# Battery.net
KiCad netlist of a schematic drawn in Altium Designer
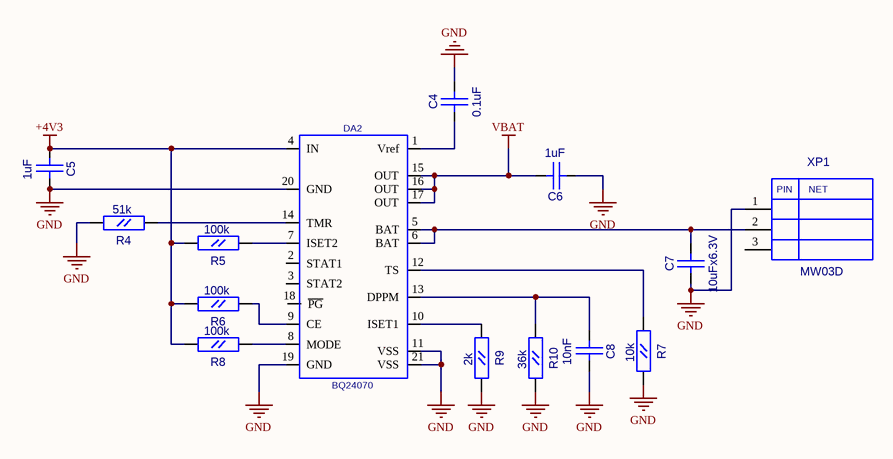
[diagram p0: Battery.SchDoc]

(export (version "E")
  (design (tool "Eeschema 10.0.6"))
  (components
    (comp (ref "C4")
      (value "0.1uF")
      (footprint "CC0603")
      (description "CC0603")
      (libsource (lib "gprs_modem_2") (part "CC0603"))
    )
    (comp (ref "C5")
      (value "1uF")
      (footprint "CC0603")
      (description "CC0603")
      (libsource (lib "gprs_modem_2") (part "CC0603"))
    )
    (comp (ref "C6")
      (value "1uF")
      (footprint "CC0603")
      (description "CC0603")
      (libsource (lib "gprs_modem_2") (part "CC0603"))
    )
    (comp (ref "C7")
      (value "10uFx6.3V")
      (footprint "CC0805")
      (description "CC0805")
      (libsource (lib "gprs_modem_2") (part "CC0805"))
    )
    (comp (ref "C8")
      (value "10nF")
      (footprint "CC0603")
      (description "CC0603")
      (libsource (lib "gprs_modem_2") (part "CC0603"))
    )
    (comp (ref "DA2")
      (value "BQ24070")
      (footprint "P-PQFP-N20")
      (libsource (lib "gprs_modem") (part "BQ24070"))
    )
    (comp (ref "R4")
      (value "51k")
      (footprint "RC0603")
      (description "RC0603")
      (libsource (lib "gprs_modem_2") (part "RC0603"))
    )
    (comp (ref "R5")
      (value "100k")
      (footprint "RC0603")
      (description "RC0603")
      (libsource (lib "gprs_modem_2") (part "RC0603"))
    )
    (comp (ref "R6")
      (value "100k")
      (footprint "RC0603")
      (description "RC0603")
      (libsource (lib "gprs_modem_2") (part "RC0603"))
    )
    (comp (ref "R7")
      (value "10k")
      (footprint "RC0603")
      (description "RC0603")
      (libsource (lib "gprs_modem_2") (part "RC0603"))
    )
    (comp (ref "R8")
      (value "100k")
      (footprint "RC0603")
      (description "RC0603")
      (libsource (lib "gprs_modem_2") (part "RC0603"))
    )
    (comp (ref "R9")
      (value "2k")
      (footprint "RC0603")
      (description "RC0603")
      (libsource (lib "gprs_modem_2") (part "RC0603"))
    )
    (comp (ref "R10")
      (value "36k")
      (footprint "RC0603")
      (description "RC0603")
      (libsource (lib "gprs_modem_2") (part "RC0603"))
    )
    (comp (ref "XP1") (value "MW03D") (footprint "MW03D") (libsource (lib "gprs_modem") (part "MW03D")))
  )
  (nets
    (net (code "1") (name "+4V3") (class "Default")
      (node (ref "C5") (pin "1") (pinfunction "A_1") (pintype "passive"))
      (node (ref "DA2") (pin "4") (pinfunction "IN_4") (pintype "passive"))
      (node (ref "R5") (pin "2") (pinfunction "B_2") (pintype "passive"))
      (node (ref "R6") (pin "2") (pinfunction "B_2") (pintype "passive"))
      (node (ref "R8") (pin "2") (pinfunction "B_2") (pintype "passive"))
    )
    (net (code "2") (name "GND") (class "Default")
      (node (ref "C4") (pin "2") (pinfunction "B_2") (pintype "passive"))
      (node (ref "C5") (pin "2") (pinfunction "B_2") (pintype "passive"))
      (node (ref "C6") (pin "1") (pinfunction "A_1") (pintype "passive"))
      (node (ref "C7") (pin "1") (pinfunction "A_1") (pintype "passive"))
      (node (ref "C8") (pin "2") (pinfunction "B_2") (pintype "passive"))
      (node (ref "DA2") (pin "11") (pinfunction "VSS_11") (pintype "passive"))
      (node (ref "DA2") (pin "19") (pinfunction "GND_19") (pintype "passive"))
      (node (ref "DA2") (pin "20") (pinfunction "GND_20") (pintype "passive"))
      (node (ref "DA2") (pin "21") (pinfunction "VSS_21") (pintype "passive"))
      (node (ref "R10") (pin "2") (pinfunction "B_2") (pintype "passive"))
      (node (ref "R4") (pin "2") (pinfunction "B_2") (pintype "passive"))
      (node (ref "R7") (pin "2") (pinfunction "B_2") (pintype "passive"))
      (node (ref "R9") (pin "2") (pinfunction "B_2") (pintype "passive"))
      (node (ref "XP1") (pin "1") (pinfunction "1_1") (pintype "passive"))
    )
    (net (code "3") (name "Net-(C4-A)") (class "Default")
      (node (ref "C4") (pin "1") (pinfunction "A_1") (pintype "passive"))
      (node (ref "DA2") (pin "1") (pinfunction "Vref_1") (pintype "passive"))
    )
    (net (code "4") (name "Net-(C7-B)") (class "Default")
      (node (ref "C7") (pin "2") (pinfunction "B_2") (pintype "passive"))
      (node (ref "DA2") (pin "5") (pinfunction "BAT_5") (pintype "passive"))
      (node (ref "DA2") (pin "6") (pinfunction "BAT_6") (pintype "passive"))
      (node (ref "XP1") (pin "2") (pinfunction "2_2") (pintype "passive"))
    )
    (net (code "5") (name "Net-(C8-A)") (class "Default")
      (node (ref "C8") (pin "1") (pinfunction "A_1") (pintype "passive"))
      (node (ref "DA2") (pin "13") (pinfunction "DPPM_13") (pintype "passive"))
      (node (ref "R10") (pin "1") (pinfunction "A_1") (pintype "passive"))
    )
    (net (code "6") (name "Net-(DA2-CE)") (class "Default")
      (node (ref "DA2") (pin "9") (pinfunction "CE_9") (pintype "passive"))
      (node (ref "R6") (pin "1") (pinfunction "A_1") (pintype "passive"))
    )
    (net (code "7") (name "Net-(DA2-ISET1)") (class "Default")
      (node (ref "DA2") (pin "10") (pinfunction "ISET1_10") (pintype "passive"))
      (node (ref "R9") (pin "1") (pinfunction "A_1") (pintype "passive"))
    )
    (net (code "8") (name "Net-(DA2-ISET2)") (class "Default")
      (node (ref "DA2") (pin "7") (pinfunction "ISET2_7") (pintype "passive"))
      (node (ref "R5") (pin "1") (pinfunction "A_1") (pintype "passive"))
    )
    (net (code "9") (name "Net-(DA2-MODE)") (class "Default")
      (node (ref "DA2") (pin "8") (pinfunction "MODE_8") (pintype "passive"))
      (node (ref "R8") (pin "1") (pinfunction "A_1") (pintype "passive"))
    )
    (net (code "10") (name "Net-(DA2-TMR)") (class "Default")
      (node (ref "DA2") (pin "14") (pinfunction "TMR_14") (pintype "passive"))
      (node (ref "R4") (pin "1") (pinfunction "A_1") (pintype "passive"))
    )
    (net (code "11") (name "Net-(DA2-TS)") (class "Default")
      (node (ref "DA2") (pin "12") (pinfunction "TS_12") (pintype "passive"))
      (node (ref "R7") (pin "1") (pinfunction "A_1") (pintype "passive"))
    )
    (net (code "12") (name "VBAT") (class "Default")
      (node (ref "C6") (pin "2") (pinfunction "B_2") (pintype "passive"))
      (node (ref "DA2") (pin "15") (pinfunction "OUT_15") (pintype "passive"))
      (node (ref "DA2") (pin "16") (pinfunction "OUT_16") (pintype "passive"))
      (node (ref "DA2") (pin "17") (pinfunction "OUT_17") (pintype "passive"))
    )
    (net (code "13") (name "unconnected-(DA2-STAT1-Pad2)") (class "Default")
      (node (ref "DA2") (pin "2") (pinfunction "STAT1_2") (pintype "passive"))
    )
    (net (code "14") (name "unconnected-(DA2-STAT2-Pad3)") (class "Default")
      (node (ref "DA2") (pin "3") (pinfunction "STAT2_3") (pintype "passive"))
    )
    (net (code "15") (name "unconnected-(DA2-~{PG}-Pad18)") (class "Default")
      (node (ref "DA2") (pin "18") (pinfunction "~{PG}_18") (pintype "passive"))
    )
    (net (code "16") (name "unconnected-(XP1-Pad3)") (class "Default")
      (node (ref "XP1") (pin "3") (pinfunction "3_3") (pintype "passive"))
    )
  )
)
